# AVC_1_0.net
KiCad netlist of a schematic drawn in EAGLE
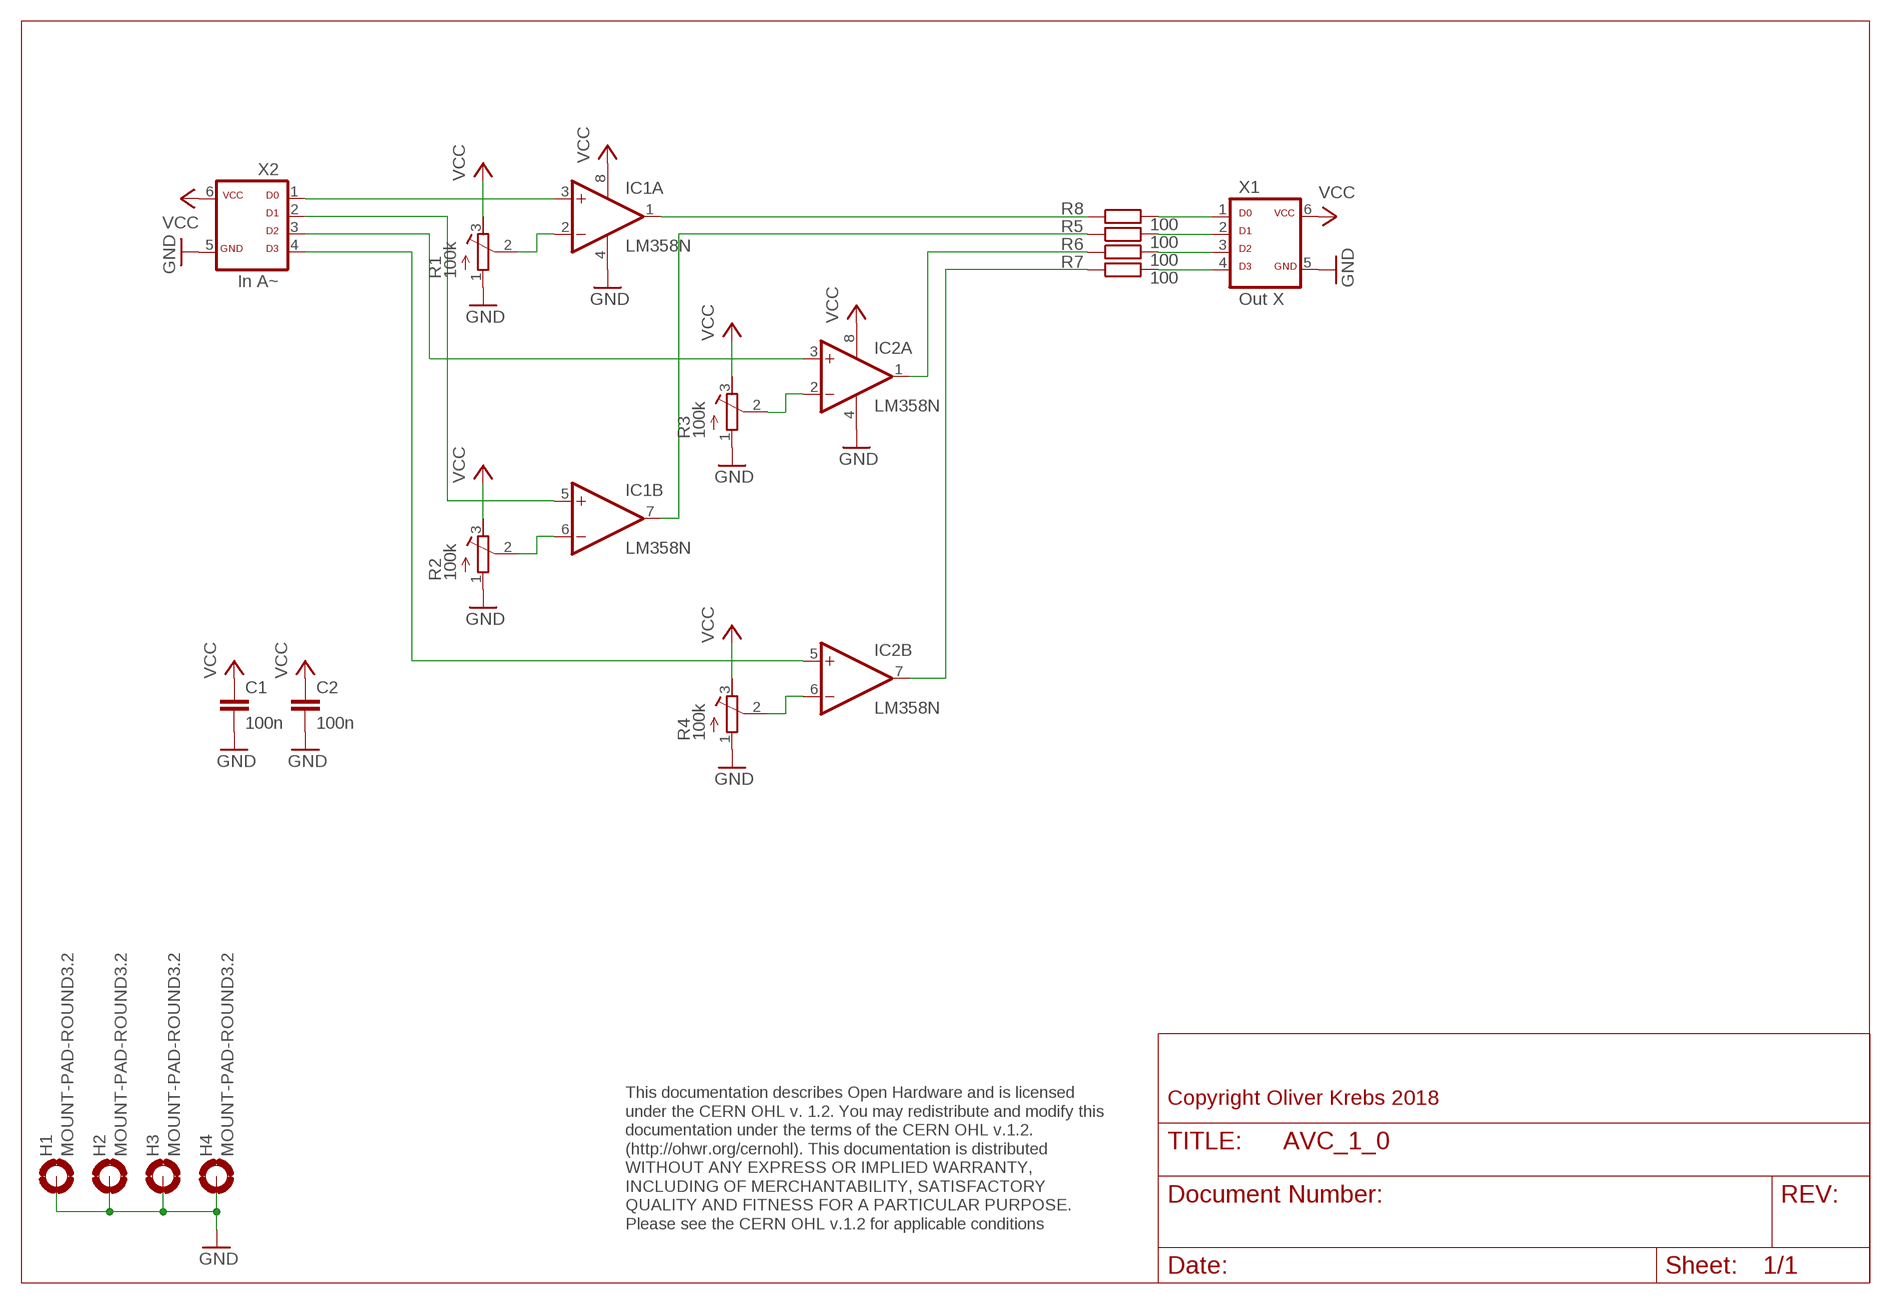
[diagram p0: schematic, sheet 1]

(export (version "E")
  (design (tool "Eeschema 10.0.6"))
  (components
    (comp (ref "C1")
      (value "100n")
      (footprint "eagle-import:C050-025X075")
      (libsource (lib "eagle-import") (part "C-EU050-025X075"))
    )
    (comp (ref "C2")
      (value "100n")
      (footprint "eagle-import:C050-025X075")
      (libsource (lib "eagle-import") (part "C-EU050-025X075"))
    )
    (comp (ref "H1")
      (value "MOUNT-PAD-ROUND3.2")
      (footprint "eagle-import:3,2-PAD")
      (libsource (lib "eagle-import") (part "MOUNT-PAD-ROUND3.2"))
    )
    (comp (ref "H2")
      (value "MOUNT-PAD-ROUND3.2")
      (footprint "eagle-import:3,2-PAD")
      (libsource (lib "eagle-import") (part "MOUNT-PAD-ROUND3.2"))
    )
    (comp (ref "H3")
      (value "MOUNT-PAD-ROUND3.2")
      (footprint "eagle-import:3,2-PAD")
      (libsource (lib "eagle-import") (part "MOUNT-PAD-ROUND3.2"))
    )
    (comp (ref "H4")
      (value "MOUNT-PAD-ROUND3.2")
      (footprint "eagle-import:3,2-PAD")
      (libsource (lib "eagle-import") (part "MOUNT-PAD-ROUND3.2"))
    )
    (comp (ref "IC1")
      (value "LM358N")
      (footprint "eagle-import:DIL08")
      (libsource (lib "eagle-import") (part "LM358N"))
    )
    (comp (ref "IC2")
      (value "LM358N")
      (footprint "eagle-import:DIL08")
      (libsource (lib "eagle-import") (part "LM358N"))
    )
    (comp (ref "R1")
      (value "100k")
      (footprint "eagle-import:ACP-6L")
      (libsource (lib "eagle-import") (part "R-TRIMMACP"))
    )
    (comp (ref "R2")
      (value "100k")
      (footprint "eagle-import:ACP-6L")
      (libsource (lib "eagle-import") (part "R-TRIMMACP"))
    )
    (comp (ref "R3")
      (value "100k")
      (footprint "eagle-import:ACP-6L")
      (libsource (lib "eagle-import") (part "R-TRIMMACP"))
    )
    (comp (ref "R4")
      (value "100k")
      (footprint "eagle-import:ACP-6L")
      (libsource (lib "eagle-import") (part "R-TRIMMACP"))
    )
    (comp (ref "R5")
      (value "100")
      (footprint "eagle-import:0207_10")
      (libsource (lib "eagle-import") (part "R-EU_0207/10"))
    )
    (comp (ref "R6")
      (value "100")
      (footprint "eagle-import:0207_10")
      (libsource (lib "eagle-import") (part "R-EU_0207/10"))
    )
    (comp (ref "R7")
      (value "100")
      (footprint "eagle-import:0207_10")
      (libsource (lib "eagle-import") (part "R-EU_0207/10"))
    )
    (comp (ref "R8")
      (value "100")
      (footprint "eagle-import:0207_10")
      (libsource (lib "eagle-import") (part "R-EU_0207/10"))
    )
    (comp (ref "X1")
      (value "Out X")
      (footprint "eagle-import:ML-6")
      (libsource (lib "eagle-import") (part "ML6D"))
    )
    (comp (ref "X2")
      (value "In A~")
      (footprint "eagle-import:ML-6")
      (libsource (lib "eagle-import") (part "ML6D"))
    )
  )
  (nets
    (net (code "1") (name "GND") (class "Default")
      (node (ref "C1") (pin "2") (pinfunction "2_2") (pintype "passive"))
      (node (ref "C2") (pin "2") (pinfunction "2_2") (pintype "passive"))
      (node (ref "H1") (pin "B3,2") (pinfunction "MOUNT_B3,2") (pintype "passive"))
      (node (ref "H2") (pin "B3,2") (pinfunction "MOUNT_B3,2") (pintype "passive"))
      (node (ref "H3") (pin "B3,2") (pinfunction "MOUNT_B3,2") (pintype "passive"))
      (node (ref "H4") (pin "B3,2") (pinfunction "MOUNT_B3,2") (pintype "passive"))
      (node (ref "IC1") (pin "4") (pinfunction "V-_4") (pintype "power_in"))
      (node (ref "IC2") (pin "4") (pinfunction "V-_4") (pintype "power_in"))
      (node (ref "R1") (pin "1") (pinfunction "A_1") (pintype "passive"))
      (node (ref "R2") (pin "1") (pinfunction "A_1") (pintype "passive"))
      (node (ref "R3") (pin "1") (pinfunction "A_1") (pintype "passive"))
      (node (ref "R4") (pin "1") (pinfunction "A_1") (pintype "passive"))
      (node (ref "X1") (pin "5") (pinfunction "5_5") (pintype "passive"))
      (node (ref "X2") (pin "5") (pinfunction "5_5") (pintype "passive"))
    )
    (net (code "2") (name "Net-(IC1A-+IN)") (class "Default")
      (node (ref "IC1") (pin "3") (pinfunction "+IN_3") (pintype "input"))
      (node (ref "X2") (pin "1") (pinfunction "1_1") (pintype "passive"))
    )
    (net (code "3") (name "Net-(IC1A--IN)") (class "Default")
      (node (ref "IC1") (pin "2") (pinfunction "-IN_2") (pintype "input"))
      (node (ref "R1") (pin "2") (pinfunction "S_2") (pintype "passive"))
    )
    (net (code "4") (name "Net-(IC1A-OUT)") (class "Default")
      (node (ref "IC1") (pin "1") (pinfunction "OUT_1") (pintype "output"))
      (node (ref "R8") (pin "1") (pinfunction "1_1") (pintype "passive"))
    )
    (net (code "5") (name "Net-(IC1B-+IN)") (class "Default")
      (node (ref "IC1") (pin "5") (pinfunction "+IN_5") (pintype "input"))
      (node (ref "X2") (pin "2") (pinfunction "2_2") (pintype "passive"))
    )
    (net (code "6") (name "Net-(IC1B--IN)") (class "Default")
      (node (ref "IC1") (pin "6") (pinfunction "-IN_6") (pintype "input"))
      (node (ref "R2") (pin "2") (pinfunction "S_2") (pintype "passive"))
    )
    (net (code "7") (name "Net-(IC1B-OUT)") (class "Default")
      (node (ref "IC1") (pin "7") (pinfunction "OUT_7") (pintype "output"))
      (node (ref "R5") (pin "1") (pinfunction "1_1") (pintype "passive"))
    )
    (net (code "8") (name "Net-(IC2A-+IN)") (class "Default")
      (node (ref "IC2") (pin "3") (pinfunction "+IN_3") (pintype "input"))
      (node (ref "X2") (pin "3") (pinfunction "3_3") (pintype "passive"))
    )
    (net (code "9") (name "Net-(IC2A--IN)") (class "Default")
      (node (ref "IC2") (pin "2") (pinfunction "-IN_2") (pintype "input"))
      (node (ref "R3") (pin "2") (pinfunction "S_2") (pintype "passive"))
    )
    (net (code "10") (name "Net-(IC2A-OUT)") (class "Default")
      (node (ref "IC2") (pin "1") (pinfunction "OUT_1") (pintype "output"))
      (node (ref "R6") (pin "1") (pinfunction "1_1") (pintype "passive"))
    )
    (net (code "11") (name "Net-(IC2B-+IN)") (class "Default")
      (node (ref "IC2") (pin "5") (pinfunction "+IN_5") (pintype "input"))
      (node (ref "X2") (pin "4") (pinfunction "4_4") (pintype "passive"))
    )
    (net (code "12") (name "Net-(IC2B--IN)") (class "Default")
      (node (ref "IC2") (pin "6") (pinfunction "-IN_6") (pintype "input"))
      (node (ref "R4") (pin "2") (pinfunction "S_2") (pintype "passive"))
    )
    (net (code "13") (name "Net-(IC2B-OUT)") (class "Default")
      (node (ref "IC2") (pin "7") (pinfunction "OUT_7") (pintype "output"))
      (node (ref "R7") (pin "1") (pinfunction "1_1") (pintype "passive"))
    )
    (net (code "14") (name "Net-(R5-Pad2)") (class "Default")
      (node (ref "R5") (pin "2") (pinfunction "2_2") (pintype "passive"))
      (node (ref "X1") (pin "2") (pinfunction "2_2") (pintype "passive"))
    )
    (net (code "15") (name "Net-(R6-Pad2)") (class "Default")
      (node (ref "R6") (pin "2") (pinfunction "2_2") (pintype "passive"))
      (node (ref "X1") (pin "3") (pinfunction "3_3") (pintype "passive"))
    )
    (net (code "16") (name "Net-(R7-Pad2)") (class "Default")
      (node (ref "R7") (pin "2") (pinfunction "2_2") (pintype "passive"))
      (node (ref "X1") (pin "4") (pinfunction "4_4") (pintype "passive"))
    )
    (net (code "17") (name "Net-(R8-Pad2)") (class "Default")
      (node (ref "R8") (pin "2") (pinfunction "2_2") (pintype "passive"))
      (node (ref "X1") (pin "1") (pinfunction "1_1") (pintype "passive"))
    )
    (net (code "18") (name "VCC") (class "Default")
      (node (ref "C1") (pin "1") (pinfunction "1_1") (pintype "passive"))
      (node (ref "C2") (pin "1") (pinfunction "1_1") (pintype "passive"))
      (node (ref "IC1") (pin "8") (pinfunction "V+_8") (pintype "power_in"))
      (node (ref "IC2") (pin "8") (pinfunction "V+_8") (pintype "power_in"))
      (node (ref "R1") (pin "3") (pinfunction "E_3") (pintype "passive"))
      (node (ref "R2") (pin "3") (pinfunction "E_3") (pintype "passive"))
      (node (ref "R3") (pin "3") (pinfunction "E_3") (pintype "passive"))
      (node (ref "R4") (pin "3") (pinfunction "E_3") (pintype "passive"))
      (node (ref "X1") (pin "6") (pinfunction "6_6") (pintype "passive"))
      (node (ref "X2") (pin "6") (pinfunction "6_6") (pintype "passive"))
    )
  )
)
